# Tachometer.net
KiCad netlist of a schematic drawn in EAGLE
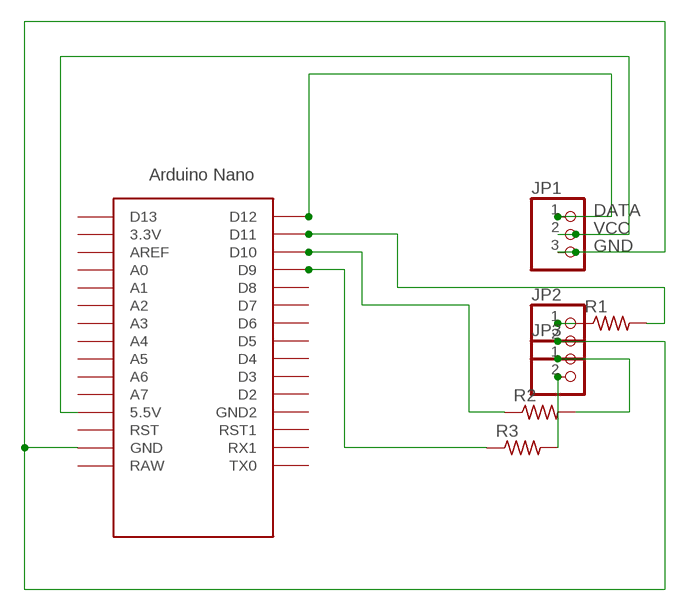
[diagram p0: schematic, sheet 1]

(export (version "E")
  (design (tool "Eeschema 10.0.6"))
  (components
    (comp (ref "JP1")
      (value "PINHD-1X3")
      (footprint "eagle-import:1X03")
      (libsource (lib "eagle-import") (part "PINHD-1X3"))
    )
    (comp (ref "JP2")
      (value "PINHD-1X2")
      (footprint "eagle-import:1X02")
      (libsource (lib "eagle-import") (part "PINHD-1X2"))
    )
    (comp (ref "JP3")
      (value "PINHD-1X2")
      (footprint "eagle-import:1X02")
      (libsource (lib "eagle-import") (part "PINHD-1X2"))
    )
    (comp (ref "R1")
      (value "R-US_0207/12")
      (footprint "eagle-import:0207_12")
      (libsource (lib "eagle-import") (part "R-US_0207/12"))
    )
    (comp (ref "R2")
      (value "R-US_0207/12")
      (footprint "eagle-import:0207_12")
      (libsource (lib "eagle-import") (part "R-US_0207/12"))
    )
    (comp (ref "R3")
      (value "R-US_0207/12")
      (footprint "eagle-import:0207_12")
      (libsource (lib "eagle-import") (part "R-US_0207/12"))
    )
    (comp (ref "U$1")
      (value "NANO")
      (footprint "eagle-import:NANO")
      (libsource (lib "eagle-import") (part "NANO"))
    )
  )
  (nets
    (net (code "1") (name "/DATA") (class "Default")
      (node (ref "JP1") (pin "1") (pinfunction "1_1") (pintype "passive"))
      (node (ref "U$1") (pin "D12") (pinfunction "D12_D12") (pintype "bidirectional"))
    )
    (net (code "2") (name "/GND") (class "Default")
      (node (ref "JP1") (pin "3") (pinfunction "3_3") (pintype "passive"))
      (node (ref "JP2") (pin "2") (pinfunction "2_2") (pintype "passive"))
      (node (ref "U$1") (pin "GND") (pinfunction "GND_GND") (pintype "bidirectional"))
    )
    (net (code "3") (name "/VCC") (class "Default")
      (node (ref "JP1") (pin "2") (pinfunction "2_2") (pintype "passive"))
      (node (ref "U$1") (pin "5V") (pinfunction "5.5V_5V") (pintype "bidirectional"))
    )
    (net (code "4") (name "Net-(JP2-Pad1)") (class "Default")
      (node (ref "JP2") (pin "1") (pinfunction "1_1") (pintype "passive"))
      (node (ref "R1") (pin "1") (pinfunction "1_1") (pintype "passive"))
    )
    (net (code "5") (name "Net-(JP3-Pad1)") (class "Default")
      (node (ref "JP3") (pin "1") (pinfunction "1_1") (pintype "passive"))
      (node (ref "R2") (pin "2") (pinfunction "2_2") (pintype "passive"))
    )
    (net (code "6") (name "Net-(JP3-Pad2)") (class "Default")
      (node (ref "JP3") (pin "2") (pinfunction "2_2") (pintype "passive"))
      (node (ref "R3") (pin "2") (pinfunction "2_2") (pintype "passive"))
    )
    (net (code "7") (name "Net-(R1-Pad2)") (class "Default")
      (node (ref "R1") (pin "2") (pinfunction "2_2") (pintype "passive"))
      (node (ref "U$1") (pin "D11") (pinfunction "D11_D11") (pintype "bidirectional"))
    )
    (net (code "8") (name "Net-(R2-Pad1)") (class "Default")
      (node (ref "R2") (pin "1") (pinfunction "1_1") (pintype "passive"))
      (node (ref "U$1") (pin "D10") (pinfunction "D10_D10") (pintype "bidirectional"))
    )
    (net (code "9") (name "Net-(R3-Pad1)") (class "Default")
      (node (ref "R3") (pin "1") (pinfunction "1_1") (pintype "passive"))
      (node (ref "U$1") (pin "D9") (pinfunction "D9_D9") (pintype "bidirectional"))
    )
    (net (code "10") (name "unconnected-(U$1-GND2-PadGND1)") (class "Default")
      (node (ref "U$1") (pin "GND1") (pinfunction "GND2_GND1") (pintype "bidirectional"))
    )
    (net (code "11") (name "unconnected-(U$1-Pad3.3V)") (class "Default")
      (node (ref "U$1") (pin "3.3V") (pinfunction "3.3V_3.3V") (pintype "bidirectional"))
    )
    (net (code "12") (name "unconnected-(U$1-PadA0)") (class "Default")
      (node (ref "U$1") (pin "A0") (pinfunction "A0_A0") (pintype "bidirectional"))
    )
    (net (code "13") (name "unconnected-(U$1-PadA1)") (class "Default")
      (node (ref "U$1") (pin "A1") (pinfunction "A1_A1") (pintype "bidirectional"))
    )
    (net (code "14") (name "unconnected-(U$1-PadA2)") (class "Default")
      (node (ref "U$1") (pin "A2") (pinfunction "A2_A2") (pintype "bidirectional"))
    )
    (net (code "15") (name "unconnected-(U$1-PadA3)") (class "Default")
      (node (ref "U$1") (pin "A3") (pinfunction "A3_A3") (pintype "bidirectional"))
    )
    (net (code "16") (name "unconnected-(U$1-PadA4)") (class "Default")
      (node (ref "U$1") (pin "A4") (pinfunction "A4_A4") (pintype "bidirectional"))
    )
    (net (code "17") (name "unconnected-(U$1-PadA5)") (class "Default")
      (node (ref "U$1") (pin "A5") (pinfunction "A5_A5") (pintype "bidirectional"))
    )
    (net (code "18") (name "unconnected-(U$1-PadA6)") (class "Default")
      (node (ref "U$1") (pin "A6") (pinfunction "A6_A6") (pintype "bidirectional"))
    )
    (net (code "19") (name "unconnected-(U$1-PadA7)") (class "Default")
      (node (ref "U$1") (pin "A7") (pinfunction "A7_A7") (pintype "bidirectional"))
    )
    (net (code "20") (name "unconnected-(U$1-PadAREF)") (class "Default")
      (node (ref "U$1") (pin "AREF") (pinfunction "AREF_AREF") (pintype "bidirectional"))
    )
    (net (code "21") (name "unconnected-(U$1-PadD2)") (class "Default")
      (node (ref "U$1") (pin "D2") (pinfunction "D2_D2") (pintype "bidirectional"))
    )
    (net (code "22") (name "unconnected-(U$1-PadD3)") (class "Default")
      (node (ref "U$1") (pin "D3") (pinfunction "D3_D3") (pintype "bidirectional"))
    )
    (net (code "23") (name "unconnected-(U$1-PadD4)") (class "Default")
      (node (ref "U$1") (pin "D4") (pinfunction "D4_D4") (pintype "bidirectional"))
    )
    (net (code "24") (name "unconnected-(U$1-PadD5)") (class "Default")
      (node (ref "U$1") (pin "D5") (pinfunction "D5_D5") (pintype "bidirectional"))
    )
    (net (code "25") (name "unconnected-(U$1-PadD6)") (class "Default")
      (node (ref "U$1") (pin "D6") (pinfunction "D6_D6") (pintype "bidirectional"))
    )
    (net (code "26") (name "unconnected-(U$1-PadD7)") (class "Default")
      (node (ref "U$1") (pin "D7") (pinfunction "D7_D7") (pintype "bidirectional"))
    )
    (net (code "27") (name "unconnected-(U$1-PadD8)") (class "Default")
      (node (ref "U$1") (pin "D8") (pinfunction "D8_D8") (pintype "bidirectional"))
    )
    (net (code "28") (name "unconnected-(U$1-PadD13)") (class "Default")
      (node (ref "U$1") (pin "D13") (pinfunction "D13_D13") (pintype "bidirectional"))
    )
    (net (code "29") (name "unconnected-(U$1-PadICSP1)") (class "Default")
      (node (ref "U$1") (pin "ICSP1") (pinfunction "ICSP1_ICSP1") (pintype "bidirectional"))
    )
    (net (code "30") (name "unconnected-(U$1-PadICSP2)") (class "Default")
      (node (ref "U$1") (pin "ICSP2") (pinfunction "ICSP2_ICSP2") (pintype "bidirectional"))
    )
    (net (code "31") (name "unconnected-(U$1-PadICSP3)") (class "Default")
      (node (ref "U$1") (pin "ICSP3") (pinfunction "ICSP3_ICSP3") (pintype "bidirectional"))
    )
    (net (code "32") (name "unconnected-(U$1-PadICSP4)") (class "Default")
      (node (ref "U$1") (pin "ICSP4") (pinfunction "ICSP4_ICSP4") (pintype "bidirectional"))
    )
    (net (code "33") (name "unconnected-(U$1-PadICSP5)") (class "Default")
      (node (ref "U$1") (pin "ICSP5") (pinfunction "ICSP5_ICSP5") (pintype "bidirectional"))
    )
    (net (code "34") (name "unconnected-(U$1-PadICSP6)") (class "Default")
      (node (ref "U$1") (pin "ICSP6") (pinfunction "ICSP6_ICSP6") (pintype "bidirectional"))
    )
    (net (code "35") (name "unconnected-(U$1-PadRAW)") (class "Default")
      (node (ref "U$1") (pin "RAW") (pinfunction "RAW_RAW") (pintype "bidirectional"))
    )
    (net (code "36") (name "unconnected-(U$1-PadRST)") (class "Default")
      (node (ref "U$1") (pin "RST") (pinfunction "RST_RST") (pintype "bidirectional"))
    )
    (net (code "37") (name "unconnected-(U$1-PadRST1)") (class "Default")
      (node (ref "U$1") (pin "RST1") (pinfunction "RST1_RST1") (pintype "bidirectional"))
    )
    (net (code "38") (name "unconnected-(U$1-PadRX1)") (class "Default")
      (node (ref "U$1") (pin "RX1") (pinfunction "RX1_RX1") (pintype "bidirectional"))
    )
    (net (code "39") (name "unconnected-(U$1-PadTX0)") (class "Default")
      (node (ref "U$1") (pin "TX0") (pinfunction "TX0_TX0") (pintype "bidirectional"))
    )
  )
)
